# Topdesign.net
KiCad netlist of a schematic drawn in Altium Designer
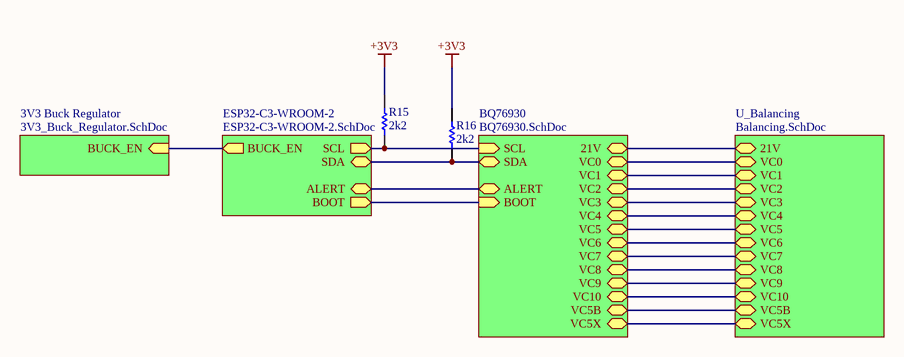
[diagram p0: Topdesign.SchDoc]

(export (version "E")
  (design (tool "Eeschema 10.0.6"))
  (components
    (comp (ref "R15")
      (value "2k2")
      (footprint "Wurth 0603 Resistor")
      (fields (field (name "Comment") "Generic Resistor 2k2 0603"))
      (libsource (lib "Passives") (part "Generic Resistor 2k2 0603"))
    )
    (comp (ref "R16")
      (value "2k2")
      (footprint "Wurth 0603 Resistor")
      (fields (field (name "Comment") "Generic Resistor 2k2 0603"))
      (libsource (lib "Passives") (part "Generic Resistor 2k2 0603"))
    )
  )
  (nets
    (net (code "1") (name "+3V3") (class "Default")
      (node (ref "R15") (pin "2") (pinfunction "2_2") (pintype "passive"))
      (node (ref "R16") (pin "2") (pinfunction "2_2") (pintype "passive"))
    )
    (net (code "6") (name "/SCL") (class "Default")
      (node (ref "R15") (pin "1") (pinfunction "1_1") (pintype "passive"))
    )
    (net (code "7") (name "/SDA") (class "Default")
      (node (ref "R16") (pin "1") (pinfunction "1_1") (pintype "passive"))
    )
  )
)
